# Sheet_1_2021-03-03.net
KiCad netlist of a schematic drawn in Altium Designer
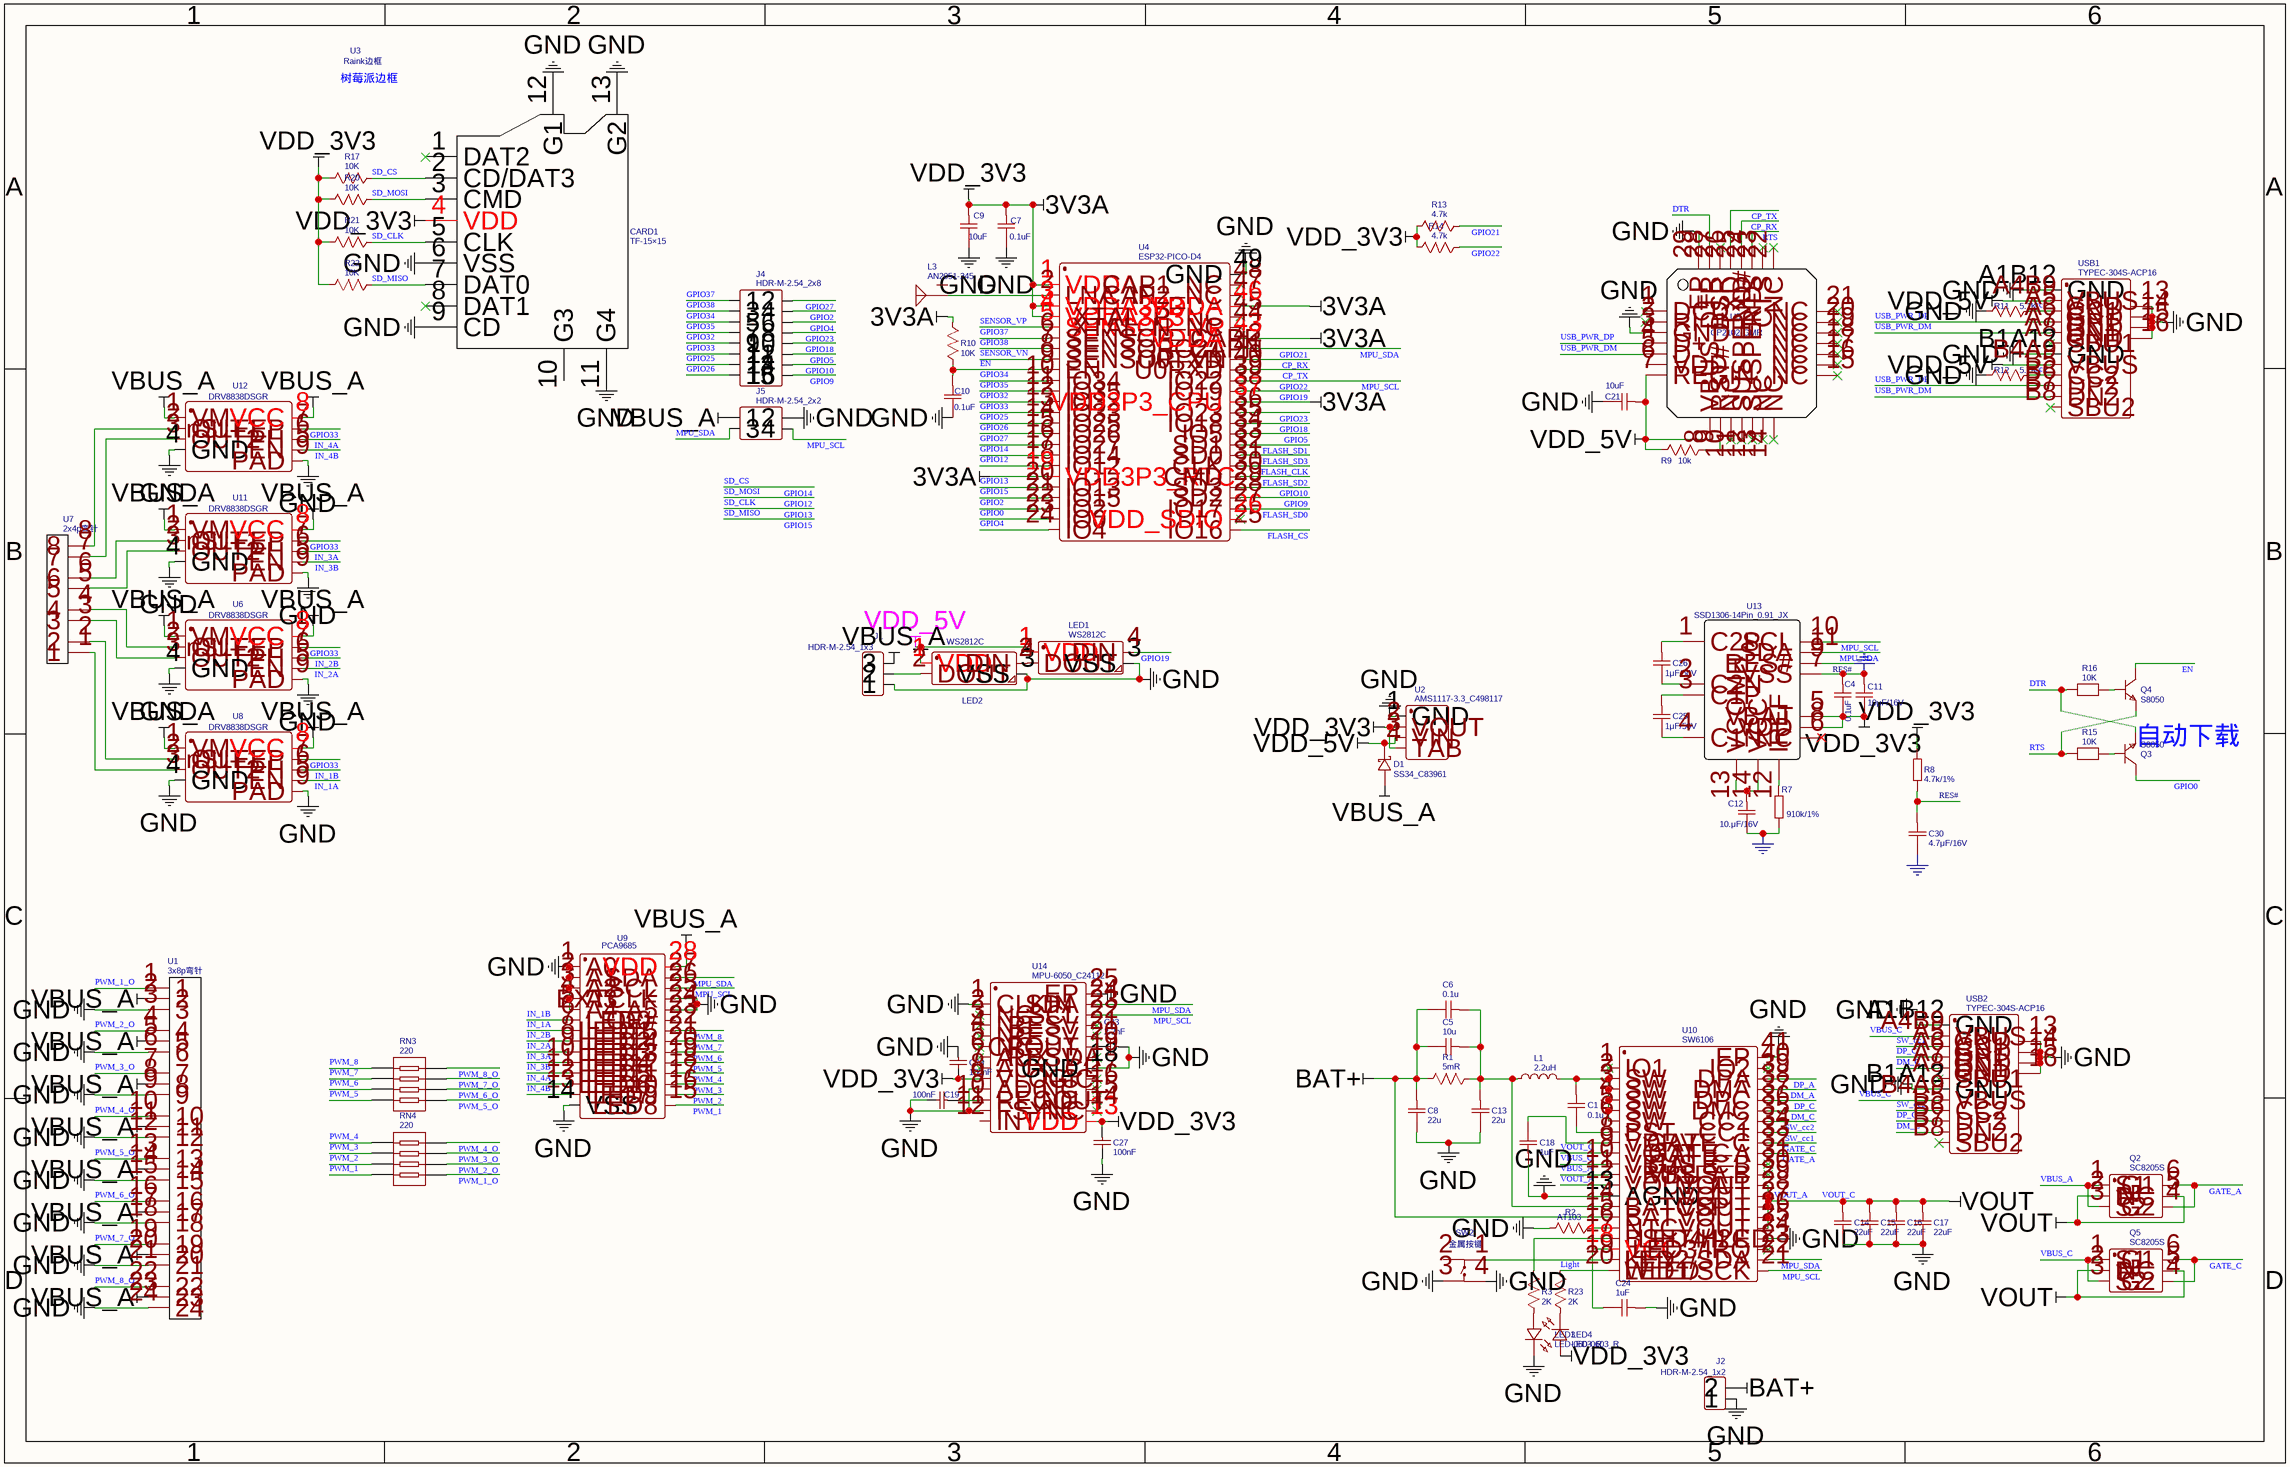
[diagram p0: Sheet_1_2021-03-03.schdoc]

(export (version "E")
  (design (tool "Eeschema 10.0.6"))
  (components
    (comp (ref "C1")
      (value "0.1u")
      (fields (field (name "CONTRIBUTOR") "LCEDA_Lib"))
      (libsource (lib "altium-import") (part "root_1_0.1u_"))
    )
    (comp (ref "C4")
      (value "0.1uF")
      (fields (field (name "CONTRIBUTOR") "LCEDA_Lib"))
      (libsource (lib "altium-import") (part "root_1_0.1uF_"))
    )
    (comp (ref "C5")
      (value "10u")
      (fields (field (name "CONTRIBUTOR") "LCEDA_Lib"))
      (libsource (lib "altium-import") (part "root_0_10u_"))
    )
    (comp (ref "C6")
      (value "0.1u")
      (fields (field (name "CONTRIBUTOR") "LCEDA_Lib"))
      (libsource (lib "altium-import") (part "root_0_0.1u_"))
    )
    (comp (ref "C7")
      (value "0.1uF")
      (fields (field (name "CONTRIBUTOR") "LCEDA_Lib"))
      (libsource (lib "altium-import") (part "root_1_0.1uF_"))
    )
    (comp (ref "C8")
      (value "22u")
      (fields (field (name "CONTRIBUTOR") "LCEDA_Lib"))
      (libsource (lib "altium-import") (part "root_1_22u_"))
    )
    (comp (ref "C9")
      (value "10uF")
      (fields (field (name "CONTRIBUTOR") "LCEDA_Lib"))
      (libsource (lib "altium-import") (part "root_1_10uF_"))
    )
    (comp (ref "C10")
      (value "0.1uF")
      (fields (field (name "CONTRIBUTOR") "LCEDA_Lib"))
      (libsource (lib "altium-import") (part "root_1_0.1uF_"))
    )
    (comp (ref "C11")
      (value "10μF/16V")
      (fields
        (field (name "BOM_SUPPLIER PART") "C326586")
        (field (name "BOM_MANUFACTURER PART") "CC0402KRX5R6BB475")
      )
      (libsource (lib "altium-import") (part "root_1_10μF/16V_"))
    )
    (comp (ref "C12")
      (value "10.μF/16V")
      (fields
        (field (name "BOM_SUPPLIER PART") "C326586")
        (field (name "BOM_MANUFACTURER PART") "CC0402KRX5R6BB475")
      )
      (libsource (lib "altium-import") (part "root_1_10.μF/16V_"))
    )
    (comp (ref "C13")
      (value "22u")
      (fields (field (name "CONTRIBUTOR") "LCEDA_Lib"))
      (libsource (lib "altium-import") (part "root_1_22u_"))
    )
    (comp (ref "C14")
      (value "22uF")
      (fields (field (name "CONTRIBUTOR") "LCEDA_Lib"))
      (libsource (lib "altium-import") (part "root_1_22uF_"))
    )
    (comp (ref "C15")
      (value "22uF")
      (fields (field (name "CONTRIBUTOR") "LCEDA_Lib"))
      (libsource (lib "altium-import") (part "root_1_22uF_"))
    )
    (comp (ref "C16")
      (value "22uF")
      (fields (field (name "CONTRIBUTOR") "LCEDA_Lib"))
      (libsource (lib "altium-import") (part "root_1_22uF_"))
    )
    (comp (ref "C17")
      (value "22uF")
      (fields (field (name "CONTRIBUTOR") "LCEDA_Lib"))
      (libsource (lib "altium-import") (part "root_1_22uF_"))
    )
    (comp (ref "C18")
      (value "1uF")
      (fields (field (name "CONTRIBUTOR") "LCEDA_Lib"))
      (libsource (lib "altium-import") (part "root_3_1uF_"))
    )
    (comp (ref "C19")
      (value "100nF")
      (fields
        (field (name "BOM_MANUFACTURER PART") "CL05B104KO5NNNC")
        (field (name "BOM_SUPPLIER PART") "C1525")
      )
      (libsource (lib "altium-import") (part "root_2_100nF_"))
    )
    (comp (ref "C21")
      (value "10uF")
      (fields (field (name "CONTRIBUTOR") "LCEDA_Lib"))
      (libsource (lib "altium-import") (part "root_0_10uF_"))
    )
    (comp (ref "C24")
      (value "1uF")
      (fields (field (name "CONTRIBUTOR") "LCEDA_Lib"))
      (libsource (lib "altium-import") (part "root_0_1uF_"))
    )
    (comp (ref "C25")
      (value "1μF/50V")
      (fields
        (field (name "BOM_SUPPLIER PART") "C29266")
        (field (name "BOM_MANUFACTURER PART") "CL05A105KO5NNNC")
      )
      (libsource (lib "altium-import") (part "root_1_1μF/50V_"))
    )
    (comp (ref "C26")
      (value "1μF/50V")
      (fields
        (field (name "BOM_SUPPLIER PART") "C29266")
        (field (name "BOM_MANUFACTURER PART") "CL05A105KO5NNNC")
      )
      (libsource (lib "altium-import") (part "root_1_1μF/50V_"))
    )
    (comp (ref "C27")
      (value "100nF")
      (fields
        (field (name "BOM_MANUFACTURER PART") "CL05B104KO5NNNC")
        (field (name "BOM_SUPPLIER PART") "C1525")
      )
      (libsource (lib "altium-import") (part "root_3_100nF_"))
    )
    (comp (ref "C28")
      (value "100nF")
      (fields
        (field (name "BOM_MANUFACTURER PART") "CL05B104KO5NNNC")
        (field (name "BOM_SUPPLIER PART") "C1525")
      )
      (libsource (lib "altium-import") (part "root_3_100nF_"))
    )
    (comp (ref "C30")
      (value "4.7μF/16V")
      (fields
        (field (name "BOM_SUPPLIER PART") "C326586")
        (field (name "BOM_MANUFACTURER PART") "CC0402KRX5R6BB475")
      )
      (libsource (lib "altium-import") (part "root_1_4.7μF/16V_"))
    )
    (comp (ref "C33")
      (value "2.2nF")
      (fields
        (field (name "BOM_MANUFACTURER PART") "0603B222K500NT")
        (field (name "BOM_SUPPLIER PART") "C1604")
      )
      (libsource (lib "altium-import") (part "root_2_2.2nF_"))
    )
    (comp (ref "CARD1")
      (value "TF-15×15")
      (fields (field (name "BOM_SUPPLIER PART") "C111196"))
      (libsource (lib "altium-import") (part "root_0_TF-15×15_"))
    )
    (comp (ref "D1")
      (value "SS34_C83961")
      (fields (field (name "BOM_MANUFACTURER PART") "SS34") (field (name "BOM_SUPPLIER PART") "C83961"))
      (libsource (lib "altium-import") (part "root_3_SS34_C83961_"))
    )
    (comp (ref "J1")
      (value "HDR-M-2.54_1x3")
      (fields (field (name "BOM_SUPPLIER PART") "C180248") (field (name "CONTRIBUTOR") "LCEDA_Lib"))
      (libsource (lib "altium-import") (part "root_2_HDR-M-2.54_1x3_"))
    )
    (comp (ref "J2")
      (value "HDR-M-2.54_1x2")
      (fields (field (name "BOM_SUPPLIER PART") "C124375") (field (name "CONTRIBUTOR") "LCEDA_Lib"))
      (libsource (lib "altium-import") (part "root_2_HDR-M-2.54_1x2_"))
    )
    (comp (ref "J4")
      (value "HDR-M-2.54_2x8")
      (fields (field (name "BOM_SUPPLIER PART") "C68234") (field (name "CONTRIBUTOR") "LCEDA_Lib"))
      (libsource (lib "altium-import") (part "root_0_HDR-M-2.54_2x8_"))
    )
    (comp (ref "J5")
      (value "HDR-M-2.54_2x2")
      (fields (field (name "BOM_SUPPLIER PART") "C66690") (field (name "CONTRIBUTOR") "LCEDA_Lib"))
      (libsource (lib "altium-import") (part "root_0_HDR-M-2.54_2x2_"))
    )
    (comp (ref "L1")
      (value "2.2uH")
      (fields
        (field (name "BOM_SUPPLIER PART") "C497893")
        (field (name "BOM_MANUFACTURER PART") "YSPI1050-2R2M")
        (field (name "CONTRIBUTOR") "LCSC")
      )
      (libsource (lib "altium-import") (part "root_0_2.2uH_"))
    )
    (comp (ref "L3")
      (value "AN2051-245")
      (fields (field (name "BOM_SUPPLIER PART") "C99727"))
      (libsource (lib "altium-import") (part "root_1_AN2051-245_"))
    )
    (comp (ref "LED1")
      (value "WS2812C")
      (fields (field (name "BOM_SUPPLIER PART") "C114587") (field (name "CONTRIBUTOR") "LCSC"))
      (libsource (lib "altium-import") (part "root_0_WS2812C_"))
    )
    (comp (ref "LED2")
      (value "WS2812C")
      (fields (field (name "BOM_SUPPLIER PART") "C114587") (field (name "CONTRIBUTOR") "LCSC"))
      (libsource (lib "altium-import") (part "root_0_WS2812C_"))
    )
    (comp (ref "LED3")
      (value "LED-0603_R")
      (fields
        (field (name "BOM_MANUFACTURER PART") "19-217/R6C-AL1M2VY/3T")
        (field (name "BOM_SUPPLIER PART") "C72044")
        (field (name "CONTRIBUTOR") "LCEDA_01")
      )
      (libsource (lib "altium-import") (part "root_3_LED-0603_R_"))
    )
    (comp (ref "LED4")
      (value "LED-0603_R")
      (fields
        (field (name "BOM_MANUFACTURER PART") "19-217/R6C-AL1M2VY/3T")
        (field (name "BOM_SUPPLIER PART") "C72044")
        (field (name "CONTRIBUTOR") "LCEDA_01")
      )
      (libsource (lib "altium-import") (part "root_1_LED-0603_R_"))
    )
    (comp (ref "Q2")
      (value "SC8205S")
      (fields (field (name "BOM_SUPPLIER PART") "C84684"))
      (libsource (lib "altium-import") (part "root_0_SC8205S_"))
    )
    (comp (ref "Q3")
      (value "S8050")
      (fields (field (name "BOM_SUPPLIER PART") "C414195") (field (name "CONTRIBUTOR") "LCSC"))
      (libsource (lib "altium-import") (part "root_0_S8050_"))
    )
    (comp (ref "Q4")
      (value "S8050")
      (fields (field (name "BOM_SUPPLIER PART") "C414195") (field (name "CONTRIBUTOR") "LCSC"))
      (libsource (lib "") (part "root_0_S8050__1"))
    )
    (comp (ref "Q5")
      (value "SC8205S")
      (fields (field (name "BOM_SUPPLIER PART") "C84684"))
      (libsource (lib "altium-import") (part "root_0_SC8205S_"))
    )
    (comp (ref "R1")
      (value "5mR")
      (fields (field (name "CONTRIBUTOR") "LCEDA_Lib"))
      (libsource (lib "altium-import") (part "root_0_5mR_"))
    )
    (comp (ref "R2")
      (value "AT103")
      (fields (field (name "CONTRIBUTOR") "LCEDA_Lib"))
      (libsource (lib "altium-import") (part "root_0_AT103_"))
    )
    (comp (ref "R3")
      (value "2K")
      (fields (field (name "CONTRIBUTOR") "LCEDA_Lib"))
      (libsource (lib "altium-import") (part "root_1_2K_"))
    )
    (comp (ref "R7")
      (value "910k/1%")
      (fields
        (field (name "BOM_SUPPLIER PART") "C137927")
        (field (name "BOM_MANUFACTURER PART") "RC0402FR-07910KL")
      )
      (libsource (lib "altium-import") (part "root_1_910k/1%_"))
    )
    (comp (ref "R8")
      (value "4.7k/1%")
      (fields
        (field (name "BOM_SUPPLIER PART") "C326586")
        (field (name "BOM_MANUFACTURER PART") "CC0402KRX5R6BB475")
      )
      (libsource (lib "altium-import") (part "root_1_4.7k/1%_"))
    )
    (comp (ref "R9")
      (value "10k")
      (fields (field (name "CONTRIBUTOR") "LCEDA_Lib"))
      (libsource (lib "altium-import") (part "root_0_10k_"))
    )
    (comp (ref "R10")
      (value "10K")
      (fields (field (name "CONTRIBUTOR") "LCEDA_Lib"))
      (libsource (lib "altium-import") (part "root_1_10K_"))
    )
    (comp (ref "R11")
      (value "5.1K")
      (fields (field (name "CONTRIBUTOR") "LCEDA_Lib"))
      (libsource (lib "altium-import") (part "root_2_5.1K_"))
    )
    (comp (ref "R12")
      (value "5.1K")
      (fields (field (name "CONTRIBUTOR") "LCEDA_Lib"))
      (libsource (lib "altium-import") (part "root_2_5.1K_"))
    )
    (comp (ref "R13")
      (value "4.7k")
      (fields (field (name "CONTRIBUTOR") "LCEDA_Lib"))
      (libsource (lib "altium-import") (part "root_0_4.7k_"))
    )
    (comp (ref "R14")
      (value "4.7k")
      (fields (field (name "CONTRIBUTOR") "LCEDA_Lib"))
      (libsource (lib "altium-import") (part "root_0_4.7k_"))
    )
    (comp (ref "R15")
      (value "10K")
      (fields
        (field (name "BOM_SUPPLIER PART") "C723584")
        (field (name "BOM_MANUFACTURER PART") "RT0402FRD0710KL")
        (field (name "CONTRIBUTOR") "LCSC")
      )
      (libsource (lib "") (part "root_0_10K__1"))
    )
    (comp (ref "R16")
      (value "10K")
      (fields
        (field (name "BOM_SUPPLIER PART") "C723584")
        (field (name "BOM_MANUFACTURER PART") "RT0402FRD0710KL")
        (field (name "CONTRIBUTOR") "LCSC")
      )
      (libsource (lib "") (part "root_0_10K__1"))
    )
    (comp (ref "R17")
      (value "10K")
      (fields (field (name "CONTRIBUTOR") "LCEDA_Lib"))
      (libsource (lib "altium-import") (part "root_0_10K_"))
    )
    (comp (ref "R20")
      (value "10K")
      (fields (field (name "CONTRIBUTOR") "LCEDA_Lib"))
      (libsource (lib "altium-import") (part "root_0_10K_"))
    )
    (comp (ref "R21")
      (value "10K")
      (fields (field (name "CONTRIBUTOR") "LCEDA_Lib"))
      (libsource (lib "altium-import") (part "root_0_10K_"))
    )
    (comp (ref "R22")
      (value "10K")
      (fields (field (name "CONTRIBUTOR") "LCEDA_Lib"))
      (libsource (lib "altium-import") (part "root_0_10K_"))
    )
    (comp (ref "R23")
      (value "2K")
      (fields (field (name "CONTRIBUTOR") "LCEDA_Lib"))
      (libsource (lib "altium-import") (part "root_1_2K_"))
    )
    (comp (ref "RN3")
      (value "220")
      (fields
        (field (name "BOM_MANUFACTURER PART") "4D03WGJ0330T5E")
        (field (name "BOM_SUPPLIER PART") "C25508")
      )
      (libsource (lib "altium-import") (part "root_0_220_"))
    )
    (comp (ref "RN4")
      (value "220")
      (fields
        (field (name "BOM_MANUFACTURER PART") "4D03WGJ0330T5E")
        (field (name "BOM_SUPPLIER PART") "C25508")
      )
      (libsource (lib "altium-import") (part "root_0_220_"))
    )
    (comp (ref "SW2")
      (value "金属按键")
      (fields
        (field (name "BOM_SUPPLIER PART") "C692460")
        (field (name "BOM_MANUFACTURER PART") "TS-1187A-B-C-B")
        (field (name "CONTRIBUTOR") "LCSC")
      )
      (libsource (lib "altium-import") (part "root_0_金属按键_"))
    )
    (comp (ref "U1")
      (value "3x8p弯针")
      (fields (field (name "CONTRIBUTOR") "Jyishit"))
      (libsource (lib "altium-import") (part "root_0_3x8p弯针_"))
    )
    (comp (ref "U2")
      (value "AMS1117-3.3_C498117")
      (fields
        (field (name "BOM_SUPPLIER PART") "C498117")
        (field (name "BOM_MANUFACTURER PART") "AMS1117-3.3")
        (field (name "CONTRIBUTOR") "LCSC")
      )
      (libsource (lib "altium-import") (part "root_0_AMS1117-3.3_C498117_"))
    )
    (comp (ref "U3")
      (value "Raink边框")
      (fields (field (name "CONTRIBUTOR") "Jyishit"))
      (libsource (lib "altium-import") (part "root_0_Raink边框_"))
    )
    (comp (ref "U4")
      (value "ESP32-PICO-D4")
      (fields (field (name "BOM_SUPPLIER PART") "C193707") (field (name "CONTRIBUTOR") "LCSC"))
      (libsource (lib "altium-import") (part "root_0_ESP32-PICO-D4_"))
    )
    (comp (ref "U5")
      (value "CP2102-GMR")
      (fields (field (name "BOM_SUPPLIER PART") "C6568"))
      (libsource (lib "altium-import") (part "root_0_CP2102-GMR_"))
    )
    (comp (ref "U6")
      (value "DRV8838DSGR")
      (fields (field (name "BOM_SUPPLIER PART") "C86667"))
      (libsource (lib "altium-import") (part "root_0_DRV8838DSGR_"))
    )
    (comp (ref "U7")
      (value "2x4p弯针")
      (fields (field (name "CONTRIBUTOR") "SinKy"))
      (libsource (lib "altium-import") (part "root_2_2x4p弯针_"))
    )
    (comp (ref "U8")
      (value "DRV8838DSGR")
      (fields (field (name "BOM_SUPPLIER PART") "C86667"))
      (libsource (lib "altium-import") (part "root_0_DRV8838DSGR_"))
    )
    (comp (ref "U9")
      (value "PCA9685")
      (fields
        (field (name "BOM_MANUFACTURER PART") "PCA9685PW/Q900,118")
        (field (name "BOM_SUPPLIER PART") "C92206")
      )
      (libsource (lib "altium-import") (part "root_0_PCA9685_"))
    )
    (comp (ref "U10")
      (value "SW6106")
      (fields (field (name "BOM_SUPPLIER PART") "C406803") (field (name "CONTRIBUTOR") "LCSC"))
      (libsource (lib "altium-import") (part "root_0_SW6106_"))
    )
    (comp (ref "U11")
      (value "DRV8838DSGR")
      (fields (field (name "BOM_SUPPLIER PART") "C86667"))
      (libsource (lib "altium-import") (part "root_0_DRV8838DSGR_"))
    )
    (comp (ref "U12")
      (value "DRV8838DSGR")
      (fields (field (name "BOM_SUPPLIER PART") "C86667"))
      (libsource (lib "altium-import") (part "root_0_DRV8838DSGR_"))
    )
    (comp (ref "U13")
      (value "SSD1306-14Pin_0.91_JX")
      (libsource (lib "altium-import") (part "root_0_SSD1306-14Pin_0.91_JX_"))
    )
    (comp (ref "U14")
      (value "MPU-6050_C24112")
      (fields (field (name "BOM_MANUFACTURER PART") "MPU-6050") (field (name "BOM_SUPPLIER PART") "C24112"))
      (libsource (lib "altium-import") (part "root_0_MPU-6050_C24112_"))
    )
    (comp (ref "USB1")
      (value "TYPEC-304S-ACP16")
      (fields (field (name "BOM_SUPPLIER PART") "C720630") (field (name "CONTRIBUTOR") "LCSC"))
      (libsource (lib "altium-import") (part "root_0_TYPEC-304S-ACP16_"))
    )
    (comp (ref "USB2")
      (value "TYPEC-304S-ACP16")
      (fields (field (name "BOM_SUPPLIER PART") "C720630") (field (name "CONTRIBUTOR") "LCSC"))
      (libsource (lib "altium-import") (part "root_0_TYPEC-304S-ACP16_"))
    )
  )
  (nets
    (net (code "1") (name "/CP_RX") (class "Default")
      (node (ref "U4") (pin "41") (pinfunction "U0TXD_41") (pintype "passive"))
      (node (ref "U5") (pin "25") (pinfunction "RXD_25") (pintype "passive"))
    )
    (net (code "2") (name "/CP_TX") (class "Default")
      (node (ref "U4") (pin "40") (pinfunction "U0RXD_40") (pintype "passive"))
      (node (ref "U5") (pin "26") (pinfunction "TXD_26") (pintype "passive"))
    )
    (net (code "3") (name "/DM_A") (class "Default")
      (node (ref "U10") (pin "38") (pinfunction "DMA_38") (pintype "passive"))
    )
    (net (code "4") (name "/DM_C") (class "Default")
      (node (ref "U10") (pin "36") (pinfunction "DMC_36") (pintype "passive"))
      (node (ref "USB2") (pin "A7") (pinfunction "DN1_A7") (pintype "passive"))
      (node (ref "USB2") (pin "B7") (pinfunction "DN2_B7") (pintype "passive"))
    )
    (net (code "5") (name "/DP_A") (class "Default")
      (node (ref "U10") (pin "39") (pinfunction "DPA_39") (pintype "passive"))
    )
    (net (code "6") (name "/DP_C") (class "Default")
      (node (ref "U10") (pin "37") (pinfunction "DPC_37") (pintype "passive"))
      (node (ref "USB2") (pin "A6") (pinfunction "DP1_A6") (pintype "passive"))
      (node (ref "USB2") (pin "B6") (pinfunction "DP2_B6") (pintype "passive"))
    )
    (net (code "7") (name "/DTR") (class "Default")
      (node (ref "Q3") (pin "2") (pinfunction "E_2") (pintype "passive"))
      (node (ref "R16") (pin "1") (pinfunction "1_1") (pintype "passive"))
      (node (ref "U5") (pin "28") (pinfunction "DTR_28") (pintype "passive"))
    )
    (net (code "8") (name "/EN") (class "Default")
      (node (ref "C10") (pin "2") (pinfunction "2_2") (pintype "passive"))
      (node (ref "Q4") (pin "3") (pinfunction "C_3") (pintype "passive"))
      (node (ref "R10") (pin "1") (pinfunction "1_1") (pintype "passive"))
      (node (ref "U4") (pin "9") (pinfunction "EN_9") (pintype "passive"))
    )
    (net (code "9") (name "/FLASH_CLK") (class "Default")
      (node (ref "U4") (pin "31") (pinfunction "CLK_31") (pintype "passive"))
    )
    (net (code "10") (name "/FLASH_CS") (class "Default")
      (node (ref "U4") (pin "25") (pinfunction "IO16_25") (pintype "passive"))
    )
    (net (code "11") (name "/FLASH_SD0") (class "Default")
      (node (ref "U4") (pin "27") (pinfunction "IO17_27") (pintype "passive"))
    )
    (net (code "12") (name "/FLASH_SD1") (class "Default")
      (node (ref "U4") (pin "33") (pinfunction "SD1_33") (pintype "passive"))
    )
    (net (code "13") (name "/FLASH_SD2") (class "Default")
      (node (ref "U4") (pin "30") (pinfunction "CMD_30") (pintype "passive"))
    )
    (net (code "14") (name "/FLASH_SD3") (class "Default")
      (node (ref "U4") (pin "32") (pinfunction "SD0_32") (pintype "passive"))
    )
    (net (code "15") (name "/GATE_A") (class "Default")
      (node (ref "Q2") (pin "4") (pinfunction "G2_4") (pintype "passive"))
      (node (ref "Q2") (pin "6") (pinfunction "G1_6") (pintype "passive"))
      (node (ref "U10") (pin "32") (pinfunction "GATE_A_32") (pintype "passive"))
    )
    (net (code "16") (name "/GATE_C") (class "Default")
      (node (ref "Q5") (pin "4") (pinfunction "G2_4") (pintype "passive"))
      (node (ref "Q5") (pin "6") (pinfunction "G1_6") (pintype "passive"))
      (node (ref "U10") (pin "33") (pinfunction "GATE_C_33") (pintype "passive"))
    )
    (net (code "17") (name "/GPIO0") (class "Default")
      (node (ref "Q3") (pin "3") (pinfunction "C_3") (pintype "passive"))
      (node (ref "U4") (pin "23") (pinfunction "IO0_23") (pintype "passive"))
    )
    (net (code "18") (name "/GPIO2") (class "Default")
      (node (ref "J4") (pin "4") (pinfunction "4_4") (pintype "passive"))
      (node (ref "U4") (pin "22") (pinfunction "IO2_22") (pintype "passive"))
    )
    (net (code "19") (name "/GPIO4") (class "Default")
      (node (ref "J4") (pin "6") (pinfunction "6_6") (pintype "passive"))
      (node (ref "U4") (pin "24") (pinfunction "IO4_24") (pintype "passive"))
    )
    (net (code "20") (name "/GPIO5") (class "Default")
      (node (ref "J4") (pin "12") (pinfunction "12_12") (pintype "passive"))
      (node (ref "U4") (pin "34") (pinfunction "IO5_34") (pintype "passive"))
    )
    (net (code "21") (name "/GPIO9") (class "Default")
      (node (ref "J4") (pin "16") (pinfunction "16_16") (pintype "passive"))
      (node (ref "U4") (pin "28") (pinfunction "SD2_28") (pintype "passive"))
    )
    (net (code "22") (name "/GPIO10") (class "Default")
      (node (ref "J4") (pin "14") (pinfunction "14_14") (pintype "passive"))
      (node (ref "U4") (pin "29") (pinfunction "SD3_29") (pintype "passive"))
    )
    (net (code "23") (name "/GPIO12") (class "Default")
      (node (ref "CARD1") (pin "3") (pinfunction "CMD_3") (pintype "passive"))
      (node (ref "R20") (pin "2") (pinfunction "2_2") (pintype "passive"))
      (node (ref "U4") (pin "18") (pinfunction "IO12_18") (pintype "passive"))
    )
    (net (code "24") (name "/GPIO13") (class "Default")
      (node (ref "CARD1") (pin "5") (pinfunction "CLK_5") (pintype "passive"))
      (node (ref "R21") (pin "2") (pinfunction "2_2") (pintype "passive"))
      (node (ref "U4") (pin "20") (pinfunction "IO13_20") (pintype "passive"))
    )
    (net (code "25") (name "/GPIO14") (class "Default")
      (node (ref "CARD1") (pin "2") (pinfunction "CD/DAT3_2") (pintype "passive"))
      (node (ref "R17") (pin "2") (pinfunction "2_2") (pintype "passive"))
      (node (ref "U4") (pin "17") (pinfunction "IO14_17") (pintype "passive"))
    )
    (net (code "26") (name "/GPIO15") (class "Default")
      (node (ref "CARD1") (pin "7") (pinfunction "DAT0_7") (pintype "passive"))
      (node (ref "R22") (pin "2") (pinfunction "2_2") (pintype "passive"))
      (node (ref "U4") (pin "21") (pinfunction "IO15_21") (pintype "passive"))
    )
    (net (code "27") (name "/GPIO18") (class "Default")
      (node (ref "J4") (pin "10") (pinfunction "10_10") (pintype "passive"))
      (node (ref "U4") (pin "35") (pinfunction "IO18_35") (pintype "passive"))
    )
    (net (code "28") (name "/GPIO19") (class "Default")
      (node (ref "LED1") (pin "4") (pinfunction "DIN_4") (pintype "passive"))
      (node (ref "U4") (pin "38") (pinfunction "IO19_38") (pintype "passive"))
    )
    (net (code "29") (name "/GPIO21") (class "Default")
      (node (ref "J5") (pin "3") (pinfunction "3_3") (pintype "passive"))
      (node (ref "R13") (pin "2") (pinfunction "2_2") (pintype "passive"))
      (node (ref "U10") (pin "22") (pinfunction "LED2/SDA_22") (pintype "passive"))
      (node (ref "U13") (pin "11") (pinfunction "SDA_11") (pintype "passive"))
      (node (ref "U14") (pin "24") (pinfunction "SDA_24") (pintype "passive"))
      (node (ref "U4") (pin "42") (pinfunction "IO21_42") (pintype "passive"))
      (node (ref "U9") (pin "27") (pinfunction "SDA_27") (pintype "passive"))
    )
    (net (code "30") (name "/GPIO22") (class "Default")
      (node (ref "J5") (pin "4") (pinfunction "4_4") (pintype "passive"))
      (node (ref "R14") (pin "2") (pinfunction "2_2") (pintype "passive"))
      (node (ref "U10") (pin "21") (pinfunction "LED1/SCK_21") (pintype "passive"))
      (node (ref "U13") (pin "10") (pinfunction "SCL_10") (pintype "passive"))
      (node (ref "U14") (pin "23") (pinfunction "SCL_23") (pintype "passive"))
      (node (ref "U4") (pin "39") (pinfunction "IO22_39") (pintype "passive"))
      (node (ref "U9") (pin "26") (pinfunction "SCL_26") (pintype "passive"))
    )
    (net (code "31") (name "/GPIO23") (class "Default")
      (node (ref "J4") (pin "8") (pinfunction "8_8") (pintype "passive"))
      (node (ref "U4") (pin "36") (pinfunction "IO23_36") (pintype "passive"))
    )
    (net (code "32") (name "/GPIO25") (class "Default")
      (node (ref "J4") (pin "13") (pinfunction "13_13") (pintype "passive"))
      (node (ref "U4") (pin "14") (pinfunction "IO25_14") (pintype "passive"))
    )
    (net (code "33") (name "/GPIO26") (class "Default")
      (node (ref "J4") (pin "15") (pinfunction "15_15") (pintype "passive"))
      (node (ref "U4") (pin "15") (pinfunction "IO26_15") (pintype "passive"))
    )
    (net (code "34") (name "/GPIO27") (class "Default")
      (node (ref "J4") (pin "2") (pinfunction "2_2") (pintype "passive"))
      (node (ref "U4") (pin "16") (pinfunction "IO27_16") (pintype "passive"))
    )
    (net (code "35") (name "/GPIO32") (class "Default")
      (node (ref "J4") (pin "9") (pinfunction "9_9") (pintype "passive"))
      (node (ref "U4") (pin "12") (pinfunction "IO32_12") (pintype "passive"))
    )
    (net (code "36") (name "/GPIO33") (class "Default")
      (node (ref "J4") (pin "11") (pinfunction "11_11") (pintype "passive"))
      (node (ref "U11") (pin "7") (pinfunction "nSLEEP_7") (pintype "passive"))
      (node (ref "U12") (pin "7") (pinfunction "nSLEEP_7") (pintype "passive"))
      (node (ref "U4") (pin "13") (pinfunction "IO33_13") (pintype "passive"))
      (node (ref "U6") (pin "7") (pinfunction "nSLEEP_7") (pintype "passive"))
      (node (ref "U8") (pin "7") (pinfunction "nSLEEP_7") (pintype "passive"))
    )
    (net (code "37") (name "/GPIO34") (class "Default")
      (node (ref "J4") (pin "5") (pinfunction "5_5") (pintype "passive"))
      (node (ref "U4") (pin "10") (pinfunction "IO34_10") (pintype "passive"))
    )
    (net (code "38") (name "/GPIO35") (class "Default")
      (node (ref "J4") (pin "7") (pinfunction "7_7") (pintype "passive"))
      (node (ref "U4") (pin "11") (pinfunction "IO35_11") (pintype "passive"))
    )
    (net (code "39") (name "/GPIO37") (class "Default")
      (node (ref "J4") (pin "1") (pinfunction "1_1") (pintype "passive"))
      (node (ref "U4") (pin "6") (pinfunction "SENSOR_CAPP_6") (pintype "passive"))
    )
    (net (code "40") (name "/GPIO38") (class "Default")
      (node (ref "J4") (pin "3") (pinfunction "3_3") (pintype "passive"))
      (node (ref "U4") (pin "7") (pinfunction "SENSOR_CAPN_7") (pintype "passive"))
    )
    (net (code "41") (name "/IN_1A") (class "Default")
      (node (ref "U8") (pin "5") (pinfunction "EN_5") (pintype "passive"))
      (node (ref "U9") (pin "7") (pinfunction "LED1_7") (pintype "passive"))
    )
    (net (code "42") (name "/IN_1B") (class "Default")
      (node (ref "U8") (pin "6") (pinfunction "PH_6") (pintype "passive"))
      (node (ref "U9") (pin "6") (pinfunction "LED0_6") (pintype "passive"))
    )
    (net (code "43") (name "/IN_2A") (class "Default")
      (node (ref "U6") (pin "5") (pinfunction "EN_5") (pintype "passive"))
      (node (ref "U9") (pin "9") (pinfunction "LED3_9") (pintype "passive"))
    )
    (net (code "44") (name "/IN_2B") (class "Default")
      (node (ref "U6") (pin "6") (pinfunction "PH_6") (pintype "passive"))
      (node (ref "U9") (pin "8") (pinfunction "LED2_8") (pintype "passive"))
    )
    (net (code "45") (name "/IN_3A") (class "Default")
      (node (ref "U11") (pin "6") (pinfunction "PH_6") (pintype "passive"))
      (node (ref "U9") (pin "10") (pinfunction "LED4_10") (pintype "passive"))
    )
    (net (code "46") (name "/IN_3B") (class "Default")
      (node (ref "U11") (pin "5") (pinfunction "EN_5") (pintype "passive"))
      (node (ref "U9") (pin "11") (pinfunction "LED5_11") (pintype "passive"))
    )
    (net (code "47") (name "/IN_4A") (class "Default")
      (node (ref "U12") (pin "6") (pinfunction "PH_6") (pintype "passive"))
      (node (ref "U9") (pin "12") (pinfunction "LED6_12") (pintype "passive"))
    )
    (net (code "48") (name "/IN_4B") (class "Default")
      (node (ref "U12") (pin "5") (pinfunction "EN_5") (pintype "passive"))
      (node (ref "U9") (pin "13") (pinfunction "LED7_13") (pintype "passive"))
    )
    (net (code "49") (name "/Light") (class "Default")
      (node (ref "R23") (pin "2") (pinfunction "2_2") (pintype "passive"))
      (node (ref "U10") (pin "20") (pinfunction "WLED_20") (pintype "passive"))
    )
    (net (code "50") (name "/PWM_1") (class "Default")
      (node (ref "RN4") (pin "4") (pinfunction "4_4") (pintype "passive"))
      (node (ref "U9") (pin "15") (pinfunction "LED8_15") (pintype "passive"))
    )
    (net (code "51") (name "/PWM_1_O") (class "Default")
      (node (ref "RN4") (pin "5") (pinfunction "5_5") (pintype "passive"))
      (node (ref "U1") (pin "1") (pinfunction "1_1") (pintype "passive"))
    )
    (net (code "52") (name "/PWM_2") (class "Default")
      (node (ref "RN4") (pin "3") (pinfunction "3_3") (pintype "passive"))
      (node (ref "U9") (pin "16") (pinfunction "LED9_16") (pintype "passive"))
    )
    (net (code "53") (name "/PWM_2_O") (class "Default")
      (node (ref "RN4") (pin "6") (pinfunction "6_6") (pintype "passive"))
      (node (ref "U1") (pin "4") (pinfunction "4_4") (pintype "passive"))
    )
    (net (code "54") (name "/PWM_3") (class "Default")
      (node (ref "RN4") (pin "2") (pinfunction "2_2") (pintype "passive"))
      (node (ref "U9") (pin "17") (pinfunction "LED10_17") (pintype "passive"))
    )
    (net (code "55") (name "/PWM_3_O") (class "Default")
      (node (ref "RN4") (pin "7") (pinfunction "7_7") (pintype "passive"))
      (node (ref "U1") (pin "7") (pinfunction "7_7") (pintype "passive"))
    )
    (net (code "56") (name "/PWM_4") (class "Default")
      (node (ref "RN4") (pin "1") (pinfunction "1_1") (pintype "passive"))
      (node (ref "U9") (pin "18") (pinfunction "LED11_18") (pintype "passive"))
    )
    (net (code "57") (name "/PWM_4_O") (class "Default")
      (node (ref "RN4") (pin "8") (pinfunction "8_8") (pintype "passive"))
      (node (ref "U1") (pin "10") (pinfunction "10_10") (pintype "passive"))
    )
    (net (code "58") (name "/PWM_5") (class "Default")
      (node (ref "RN3") (pin "4") (pinfunction "4_4") (pintype "passive"))
      (node (ref "U9") (pin "19") (pinfunction "LED12_19") (pintype "passive"))
    )
    (net (code "59") (name "/PWM_5_O") (class "Default")
      (node (ref "RN3") (pin "5") (pinfunction "5_5") (pintype "passive"))
      (node (ref "U1") (pin "13") (pinfunction "13_13") (pintype "passive"))
    )
    (net (code "60") (name "/PWM_6") (class "Default")
      (node (ref "RN3") (pin "3") (pinfunction "3_3") (pintype "passive"))
      (node (ref "U9") (pin "20") (pinfunction "LED13_20") (pintype "passive"))
    )
    (net (code "61") (name "/PWM_6_O") (class "Default")
      (node (ref "RN3") (pin "6") (pinfunction "6_6") (pintype "passive"))
      (node (ref "U1") (pin "16") (pinfunction "16_16") (pintype "passive"))
    )
    (net (code "62") (name "/PWM_7") (class "Default")
      (node (ref "RN3") (pin "2") (pinfunction "2_2") (pintype "passive"))
      (node (ref "U9") (pin "21") (pinfunction "LED14_21") (pintype "passive"))
    )
    (net (code "63") (name "/PWM_7_O") (class "Default")
      (node (ref "RN3") (pin "7") (pinfunction "7_7") (pintype "passive"))
      (node (ref "U1") (pin "19") (pinfunction "19_19") (pintype "passive"))
    )
    (net (code "64") (name "/PWM_8") (class "Default")
      (node (ref "RN3") (pin "1") (pinfunction "1_1") (pintype "passive"))
      (node (ref "U9") (pin "22") (pinfunction "LED15_22") (pintype "passive"))
    )
    (net (code "65") (name "/PWM_8_O") (class "Default")
      (node (ref "RN3") (pin "8") (pinfunction "8_8") (pintype "passive"))
      (node (ref "U1") (pin "22") (pinfunction "22_22") (pintype "passive"))
    )
    (net (code "66") (name "/RES#") (class "Default")
      (node (ref "C30") (pin "2") (pinfunction "2_2") (pintype "passive"))
      (node (ref "R8") (pin "1") (pinfunction "1_1") (pintype "passive"))
      (node (ref "U13") (pin "9") (pinfunction "RES#_9") (pintype "passive"))
    )
    (net (code "67") (name "/RTS") (class "Default")
      (node (ref "Q4") (pin "2") (pinfunction "E_2") (pintype "passive"))
      (node (ref "R15") (pin "1") (pinfunction "1_1") (pintype "passive"))
      (node (ref "U5") (pin "24") (pinfunction "RTS_24") (pintype "passive"))
    )
    (net (code "68") (name "/SENSOR_VN") (class "Default")
      (node (ref "U4") (pin "8") (pinfunction "SENSOR_VN_8") (pintype "passive"))
    )
    (net (code "69") (name "/SENSOR_VP") (class "Default")
      (node (ref "U4") (pin "5") (pinfunction "SENSOR_VP_5") (pintype "passive"))
    )
    (net (code "70") (name "/SW_cc1") (class "Default")
      (node (ref "U10") (pin "34") (pinfunction "CC1_34") (pintype "passive"))
      (node (ref "USB2") (pin "A5") (pinfunction "CC1_A5") (pintype "passive"))
    )
    (net (code "71") (name "/SW_cc2") (class "Default")
      (node (ref "U10") (pin "35") (pinfunction "CC2_35") (pintype "passive"))
      (node (ref "USB2") (pin "B5") (pinfunction "CC2_B5") (pintype "passive"))
    )
    (net (code "72") (name "/USB_PWR_DM") (class "Default")
      (node (ref "U5") (pin "5") (pinfunction "D-_5") (pintype "passive"))
      (node (ref "USB1") (pin "A7") (pinfunction "DN1_A7") (pintype "passive"))
      (node (ref "USB1") (pin "B7") (pinfunction "DN2_B7") (pintype "passive"))
    )
    (net (code "73") (name "/USB_PWR_DP") (class "Default")
      (node (ref "U5") (pin "4") (pinfunction "D+_4") (pintype "passive"))
      (node (ref "USB1") (pin "A6") (pinfunction "DP1_A6") (pintype "passive"))
      (node (ref "USB1") (pin "B6") (pinfunction "DP2_B6") (pintype "passive"))
    )
    (net (code "74") (name "/VBUS_C") (class "Default")
      (node (ref "Q5") (pin "1") (pinfunction "S1_1") (pintype "passive"))
      (node (ref "Q5") (pin "3") (pinfunction "S2_3") (pintype "passive"))
      (node (ref "U10") (pin "10") (pinfunction "VBUS_C_10") (pintype "passive"))
      (node (ref "USB2") (pin "A4B9") (pinfunction "VBUS_A4B9") (pintype "passive"))
      (node (ref "USB2") (pin "B4A9") (pinfunction "VBUS_B4A9") (pintype "passive"))
    )
    (net (code "75") (name "/cc1") (class "Default")
      (node (ref "R11") (pin "1") (pinfunction "1_1") (pintype "passive"))
      (node (ref "USB1") (pin "A5") (pinfunction "CC1_A5") (pintype "passive"))
    )
    (net (code "76") (name "/cc2") (class "Default")
      (node (ref "R12") (pin "1") (pinfunction "1_1") (pintype "passive"))
      (node (ref "USB1") (pin "B5") (pinfunction "CC2_B5") (pintype "passive"))
    )
    (net (code "77") (name "3V3A") (class "Default")
      (node (ref "C11") (pin "1") (pinfunction "1_1") (pintype "passive"))
      (node (ref "C27") (pin "1") (pinfunction "1_1") (pintype "passive"))
      (node (ref "C28") (pin "2") (pinfunction "2_2") (pintype "passive"))
      (node (ref "C4") (pin "1") (pinfunction "1_1") (pintype "passive"))
      (node (ref "C7") (pin "2") (pinfunction "2_2") (pintype "passive"))
      (node (ref "C9") (pin "2") (pinfunction "2_2") (pintype "passive"))
      (node (ref "CARD1") (pin "4") (pinfunction "VDD_4") (pintype "passive"))
      (node (ref "LED4") (pin "1") (pinfunction "1_1") (pintype "passive"))
      (node (ref "R10") (pin "2") (pinfunction "2_2") (pintype "passive"))
      (node (ref "R13") (pin "1") (pinfunction "1_1") (pintype "passive"))
      (node (ref "R14") (pin "1") (pinfunction "1_1") (pintype "passive"))
      (node (ref "R17") (pin "1") (pinfunction "1_1") (pintype "passive"))
      (node (ref "R20") (pin "1") (pinfunction "1_1") (pintype "passive"))
      (node (ref "R21") (pin "1") (pinfunction "1_1") (pintype "passive"))
      (node (ref "R22") (pin "1") (pinfunction "1_1") (pintype "passive"))
      (node (ref "R8") (pin "2") (pinfunction "2_2") (pintype "passive"))
      (node (ref "U13") (pin "5") (pinfunction "VBAT_5") (pintype "passive"))
      (node (ref "U13") (pin "8") (pinfunction "VDD_8") (pintype "passive"))
      (node (ref "U14") (pin "13") (pinfunction "VDD_13") (pintype "passive"))
      (node (ref "U14") (pin "8") (pinfunction "VLOGIC_8") (pintype "passive"))
      (node (ref "U2") (pin "2") (pinfunction "VOUT_2") (pintype "passive"))
      (node (ref "U2") (pin "4") (pinfunction "TAB_4") (pintype "passive"))
      (node (ref "U4") (pin "1") (pinfunction "VDDA_1") (pintype "passive"))
      (node (ref "U4") (pin "19") (pinfunction "VDD3P3_RTC_19") (pintype "passive"))
      (node (ref "U4") (pin "3") (pinfunction "VDDA3P3_3") (pintype "passive"))
      (node (ref "U4") (pin "37") (pinfunction "VDD3P3_CPU_37") (pintype "passive"))
      (node (ref "U4") (pin "4") (pinfunction "VDDA3P3_4") (pintype "passive"))
      (node (ref "U4") (pin "43") (pinfunction "VDDA_43") (pintype "passive"))
      (node (ref "U4") (pin "46") (pinfunction "VDDA_46") (pintype "passive"))
    )
    (net (code "78") (name "BAT+") (class "Default")
      (node (ref "C5") (pin "1") (pinfunction "1_1") (pintype "passive"))
      (node (ref "C6") (pin "1") (pinfunction "1_1") (pintype "passive"))
      (node (ref "C8") (pin "2") (pinfunction "2_2") (pintype "passive"))
      (node (ref "J2") (pin "2") (pinfunction "2_2") (pintype "passive"))
      (node (ref "R1") (pin "1") (pinfunction "1_1") (pintype "passive"))
      (node (ref "U10") (pin "15") (pinfunction "BAT_15") (pintype "passive"))
    )
    (net (code "79") (name "GND") (class "Default")
      (node (ref "C10") (pin "1") (pinfunction "1_1") (pintype "passive"))
      (node (ref "C11") (pin "2") (pinfunction "2_2") (pintype "passive"))
      (node (ref "C12") (pin "1") (pinfunction "1_1") (pintype "passive"))
      (node (ref "C13") (pin "1") (pinfunction "1_1") (pintype "passive"))
      (node (ref "C14") (pin "1") (pinfunction "1_1") (pintype "passive"))
      (node (ref "C15") (pin "1") (pinfunction "1_1") (pintype "passive"))
      (node (ref "C16") (pin "1") (pinfunction "1_1") (pintype "passive"))
      (node (ref "C17") (pin "1") (pinfunction "1_1") (pintype "passive"))
      (node (ref "C18") (pin "2") (pinfunction "2_2") (pintype "passive"))
      (node (ref "C19") (pin "2") (pinfunction "2_2") (pintype "passive"))
      (node (ref "C21") (pin "1") (pinfunction "1_1") (pintype "passive"))
      (node (ref "C24") (pin "2") (pinfunction "2_2") (pintype "passive"))
      (node (ref "C27") (pin "2") (pinfunction "2_2") (pintype "passive"))
      (node (ref "C28") (pin "1") (pinfunction "1_1") (pintype "passive"))
      (node (ref "C30") (pin "1") (pinfunction "1_1") (pintype "passive"))
      (node (ref "C33") (pin "1") (pinfunction "1_1") (pintype "passive"))
      (node (ref "C4") (pin "2") (pinfunction "2_2") (pintype "passive"))
      (node (ref "C7") (pin "1") (pinfunction "1_1") (pintype "passive"))
      (node (ref "C8") (pin "1") (pinfunction "1_1") (pintype "passive"))
      (node (ref "C9") (pin "1") (pinfunction "1_1") (pintype "passive"))
      (node (ref "CARD1") (pin "11") (pinfunction "G4_11") (pintype "passive"))
      (node (ref "CARD1") (pin "12") (pinfunction "G1_12") (pintype "passive"))
      (node (ref "CARD1") (pin "13") (pinfunction "G2_13") (pintype "passive"))
      (node (ref "CARD1") (pin "6") (pinfunction "VSS_6") (pintype "passive"))
      (node (ref "CARD1") (pin "9") (pinfunction "CD_9") (pintype "passive"))
      (node (ref "J1") (pin "1") (pinfunction "1_1") (pintype "passive"))
      (node (ref "J2") (pin "1") (pinfunction "1_1") (pintype "passive"))
      (node (ref "J5") (pin "2") (pinfunction "2_2") (pintype "passive"))
      (node (ref "LED1") (pin "3") (pinfunction "VSS_3") (pintype "passive"))
      (node (ref "LED2") (pin "3") (pinfunction "VSS_3") (pintype "passive"))
      (node (ref "LED3") (pin "2") (pinfunction "2_2") (pintype "passive"))
      (node (ref "R11") (pin "2") (pinfunction "2_2") (pintype "passive"))
      (node (ref "R12") (pin "2") (pinfunction "2_2") (pintype "passive"))
      (node (ref "R2") (pin "1") (pinfunction "1_1") (pintype "passive"))
      (node (ref "R7") (pin "1") (pinfunction "1_1") (pintype "passive"))
      (node (ref "SW2") (pin "3") (pinfunction "3_3") (pintype "passive"))
      (node (ref "SW2") (pin "4") (pinfunction "4_4") (pintype "passive"))
      (node (ref "U1") (pin "12") (pinfunction "12_12") (pintype "passive"))
      (node (ref "U1") (pin "15") (pinfunction "15_15") (pintype "passive"))
      (node (ref "U1") (pin "18") (pinfunction "18_18") (pintype "passive"))
      (node (ref "U1") (pin "21") (pinfunction "21_21") (pintype "passive"))
      (node (ref "U1") (pin "24") (pinfunction "24_24") (pintype "passive"))
      (node (ref "U1") (pin "3") (pinfunction "3_3") (pintype "passive"))
      (node (ref "U1") (pin "6") (pinfunction "6_6") (pintype "passive"))
      (node (ref "U1") (pin "9") (pinfunction "9_9") (pintype "passive"))
      (node (ref "U10") (pin "13") (pinfunction "AGND_13") (pintype "passive"))
      (node (ref "U10") (pin "24") (pinfunction "LED4/I2C_24") (pintype "passive"))
      (node (ref "U10") (pin "41") (pinfunction "EP_41") (pintype "passive"))
      (node (ref "U11") (pin "4") (pinfunction "GND_4") (pintype "passive"))
      (node (ref "U11") (pin "9") (pinfunction "PAD_9") (pintype "passive"))
      (node (ref "U12") (pin "4") (pinfunction "GND_4") (pintype "passive"))
      (node (ref "U12") (pin "9") (pinfunction "PAD_9") (pintype "passive"))
      (node (ref "U13") (pin "7") (pinfunction "VSS_7") (pintype "passive"))
      (node (ref "U14") (pin "1") (pinfunction "CLKIN_1") (pintype "passive"))
      (node (ref "U14") (pin "11") (pinfunction "FSYNC_11") (pintype "passive"))
      (node (ref "U14") (pin "18") (pinfunction "GND_18") (pintype "passive"))
      (node (ref "U14") (pin "25") (pinfunction "EP_25") (pintype "passive"))
      (node (ref "U14") (pin "9") (pinfunction "AD0_9") (pintype "passive"))
      (node (ref "U2") (pin "1") (pinfunction "GND_1") (pintype "passive"))
      (node (ref "U4") (pin "49") (pinfunction "GND_49") (pintype "passive"))
      (node (ref "U5") (pin "29") (pinfunction "EP_29") (pintype "passive"))
      (node (ref "U5") (pin "3") (pinfunction "GND_3") (pintype "passive"))
      (node (ref "U6") (pin "4") (pinfunction "GND_4") (pintype "passive"))
      (node (ref "U6") (pin "9") (pinfunction "PAD_9") (pintype "passive"))
      (node (ref "U8") (pin "4") (pinfunction "GND_4") (pintype "passive"))
      (node (ref "U8") (pin "9") (pinfunction "PAD_9") (pintype "passive"))
      (node (ref "U9") (pin "1") (pinfunction "A0_1") (pintype "passive"))
      (node (ref "U9") (pin "14") (pinfunction "VSS_14") (pintype "passive"))
      (node (ref "U9") (pin "2") (pinfunction "A1_2") (pintype "passive"))
      (node (ref "U9") (pin "24") (pinfunction "A5_24") (pintype "passive"))
      (node (ref "U9") (pin "25") (pinfunction "EXTCLK_25") (pintype "passive"))
      (node (ref "U9") (pin "3") (pinfunction "A2_3") (pintype "passive"))
      (node (ref "U9") (pin "4") (pinfunction "A3_4") (pintype "passive"))
      (node (ref "U9") (pin "5") (pinfunction "A4_5") (pintype "passive"))
      (node (ref "USB1") (pin "13") (pinfunction "GND_13") (pintype "passive"))
      (node (ref "USB1") (pin "14") (pinfunction "GND_14") (pintype "passive"))
      (node (ref "USB1") (pin "15") (pinfunction "GND_15") (pintype "passive"))
      (node (ref "USB1") (pin "16") (pinfunction "GND_16") (pintype "passive"))
      (node (ref "USB1") (pin "A1B12") (pinfunction "GND_A1B12") (pintype "passive"))
      (node (ref "USB1") (pin "B1A12") (pinfunction "GND_B1A12") (pintype "passive"))
      (node (ref "USB2") (pin "13") (pinfunction "GND_13") (pintype "passive"))
      (node (ref "USB2") (pin "14") (pinfunction "GND_14") (pintype "passive"))
      (node (ref "USB2") (pin "15") (pinfunction "GND_15") (pintype "passive"))
      (node (ref "USB2") (pin "16") (pinfunction "GND_16") (pintype "passive"))
      (node (ref "USB2") (pin "A1B12") (pinfunction "GND_A1B12") (pintype "passive"))
      (node (ref "USB2") (pin "B1A12") (pinfunction "GND_B1A12") (pintype "passive"))
    )
    (net (code "80") (name "Net-(C1-Pad2)") (class "Default")
      (node (ref "C1") (pin "2") (pinfunction "2_2") (pintype "passive"))
      (node (ref "L1") (pin "2") (pinfunction "2_2") (pintype "passive"))
      (node (ref "U10") (pin "2") (pinfunction "SW_2") (pintype "passive"))
      (node (ref "U10") (pin "3") (pinfunction "SW_3") (pintype "passive"))
      (node (ref "U10") (pin "4") (pinfunction "SW_4") (pintype "passive"))
      (node (ref "U10") (pin "5") (pinfunction "SW_5") (pintype "passive"))
      (node (ref "U10") (pin "6") (pinfunction "SW_6") (pintype "passive"))
    )
    (net (code "81") (name "Net-(L3-ANT)") (class "Default")
      (node (ref "L3") (pin "1") (pinfunction "ANT_1") (pintype "passive"))
      (node (ref "U4") (pin "2") (pinfunction "LNA_IN_2") (pintype "passive"))
    )
    (net (code "82") (name "Net-(LED1-DOUT)") (class "Default")
      (node (ref "LED1") (pin "2") (pinfunction "DOUT_2") (pintype "passive"))
      (node (ref "LED2") (pin "4") (pinfunction "DIN_4") (pintype "passive"))
    )
    (net (code "83") (name "Net-(LED2-DOUT)") (class "Default")
      (node (ref "J1") (pin "2") (pinfunction "2_2") (pintype "passive"))
      (node (ref "LED2") (pin "2") (pinfunction "DOUT_2") (pintype "passive"))
    )
    (net (code "84") (name "Net-(LED3-Pad1)") (class "Default")
      (node (ref "LED3") (pin "1") (pinfunction "1_1") (pintype "passive"))
      (node (ref "R3") (pin "1") (pinfunction "1_1") (pintype "passive"))
    )
    (net (code "85") (name "Net-(LED4-Pad2)") (class "Default")
      (node (ref "LED4") (pin "2") (pinfunction "2_2") (pintype "passive"))
      (node (ref "R23") (pin "1") (pinfunction "1_1") (pintype "passive"))
    )
    (net (code "86") (name "Net-(Q3-B)") (class "Default")
      (node (ref "Q3") (pin "1") (pinfunction "B_1") (pintype "passive"))
      (node (ref "R15") (pin "2") (pinfunction "2_2") (pintype "passive"))
    )
    (net (code "87") (name "Net-(Q4-B)") (class "Default")
      (node (ref "Q4") (pin "1") (pinfunction "B_1") (pintype "passive"))
      (node (ref "R16") (pin "2") (pinfunction "2_2") (pintype "passive"))
    )
    (net (code "88") (name "Net-(U5-RST#)") (class "Default")
      (node (ref "R9") (pin "2") (pinfunction "2_2") (pintype "passive"))
      (node (ref "U5") (pin "9") (pinfunction "RST#_9") (pintype "passive"))
    )
    (net (code "89") (name "Net-(U6-OUT1)") (class "Default")
      (node (ref "U6") (pin "2") (pinfunction "OUT1_2") (pintype "passive"))
      (node (ref "U7") (pin "4") (pinfunction "4_4") (pintype "passive"))
    )
    (net (code "90") (name "Net-(U6-OUT2)") (class "Default")
      (node (ref "U6") (pin "3") (pinfunction "OUT2_3") (pintype "passive"))
      (node (ref "U7") (pin "3") (pinfunction "3_3") (pintype "passive"))
    )
    (net (code "91") (name "Net-(U8-OUT1)") (class "Default")
      (node (ref "U7") (pin "2") (pinfunction "2_2") (pintype "passive"))
      (node (ref "U8") (pin "2") (pinfunction "OUT1_2") (pintype "passive"))
    )
    (net (code "92") (name "Net-(U8-OUT2)") (class "Default")
      (node (ref "U7") (pin "1") (pinfunction "1_1") (pintype "passive"))
      (node (ref "U8") (pin "3") (pinfunction "OUT2_3") (pintype "passive"))
    )
    (net (code "93") (name "Net-(U10-BATCSP)") (class "Default")
      (node (ref "C13") (pin "2") (pinfunction "2_2") (pintype "passive"))
      (node (ref "C5") (pin "2") (pinfunction "2_2") (pintype "passive"))
      (node (ref "C6") (pin "2") (pinfunction "2_2") (pintype "passive"))
      (node (ref "L1") (pin "1") (pinfunction "1_1") (pintype "passive"))
      (node (ref "R1") (pin "2") (pinfunction "2_2") (pintype "passive"))
      (node (ref "U10") (pin "14") (pinfunction "BATCSP_14") (pintype "passive"))
    )
    (net (code "94") (name "Net-(U10-BSET{slash}HLED)") (class "Default")
      (node (ref "R3") (pin "2") (pinfunction "2_2") (pintype "passive"))
      (node (ref "U10") (pin "17") (pinfunction "BSET/HLED_17") (pintype "passive"))
    )
    (net (code "95") (name "Net-(U10-BST)") (class "Default")
      (node (ref "C1") (pin "1") (pinfunction "1_1") (pintype "passive"))
      (node (ref "U10") (pin "7") (pinfunction "BST_7") (pintype "passive"))
    )
    (net (code "96") (name "Net-(U10-KEY)") (class "Default")
      (node (ref "SW2") (pin "1") (pinfunction "1_1") (pintype "passive"))
      (node (ref "U10") (pin "19") (pinfunction "KEY_19") (pintype "passive"))
    )
    (net (code "97") (name "Net-(U10-NTC)") (class "Default")
      (node (ref "R2") (pin "2") (pinfunction "2_2") (pintype "passive"))
      (node (ref "U10") (pin "16") (pinfunction "NTC_16") (pintype "passive"))
    )
    (net (code "98") (name "Net-(U10-VCC)") (class "Default")
      (node (ref "C24") (pin "1") (pinfunction "1_1") (pintype "passive"))
      (node (ref "U10") (pin "18") (pinfunction "VCC_18") (pintype "passive"))
    )
    (net (code "99") (name "Net-(U10-VDRV)") (class "Default")
      (node (ref "C18") (pin "1") (pinfunction "1_1") (pintype "passive"))
      (node (ref "U10") (pin "8") (pinfunction "VDRV_8") (pintype "passive"))
    )
    (net (code "100") (name "Net-(U11-OUT1)") (class "Default")
      (node (ref "U11") (pin "2") (pinfunction "OUT1_2") (pintype "passive"))
      (node (ref "U7") (pin "6") (pinfunction "6_6") (pintype "passive"))
    )
    (net (code "101") (name "Net-(U11-OUT2)") (class "Default")
      (node (ref "U11") (pin "3") (pinfunction "OUT2_3") (pintype "passive"))
      (node (ref "U7") (pin "5") (pinfunction "5_5") (pintype "passive"))
    )
    (net (code "102") (name "Net-(U12-OUT1)") (class "Default")
      (node (ref "U12") (pin "2") (pinfunction "OUT1_2") (pintype "passive"))
      (node (ref "U7") (pin "8") (pinfunction "8_8") (pintype "passive"))
    )
    (net (code "103") (name "Net-(U12-OUT2)") (class "Default")
      (node (ref "U12") (pin "3") (pinfunction "OUT2_3") (pintype "passive"))
      (node (ref "U7") (pin "7") (pinfunction "7_7") (pintype "passive"))
    )
    (net (code "104") (name "Net-(U13-C1N)") (class "Default")
      (node (ref "C25") (pin "1") (pinfunction "1_1") (pintype "passive"))
      (node (ref "U13") (pin "4") (pinfunction "C1N_4") (pintype "passive"))
    )
    (net (code "105") (name "Net-(U13-C1P)") (class "Default")
      (node (ref "C25") (pin "2") (pinfunction "2_2") (pintype "passive"))
      (node (ref "U13") (pin "3") (pinfunction "C1P_3") (pintype "passive"))
    )
    (net (code "106") (name "Net-(U13-C2N)") (class "Default")
      (node (ref "C26") (pin "1") (pinfunction "1_1") (pintype "passive"))
      (node (ref "U13") (pin "2") (pinfunction "C2N_2") (pintype "passive"))
    )
    (net (code "107") (name "Net-(U13-C2P)") (class "Default")
      (node (ref "C26") (pin "2") (pinfunction "2_2") (pintype "passive"))
      (node (ref "U13") (pin "1") (pinfunction "C2P_1") (pintype "passive"))
    )
    (net (code "108") (name "Net-(U13-IREF)") (class "Default")
      (node (ref "R7") (pin "2") (pinfunction "2_2") (pintype "passive"))
      (node (ref "U13") (pin "12") (pinfunction "IREF_12") (pintype "passive"))
    )
    (net (code "109") (name "Net-(U13-VCC)") (class "Default")
      (node (ref "C12") (pin "2") (pinfunction "2_2") (pintype "passive"))
      (node (ref "U13") (pin "13") (pinfunction "VCOMH_13") (pintype "passive"))
      (node (ref "U13") (pin "14") (pinfunction "VCC_14") (pintype "passive"))
    )
    (net (code "110") (name "Net-(U14-CPOUT)") (class "Default")
      (node (ref "C33") (pin "2") (pinfunction "2_2") (pintype "passive"))
      (node (ref "U14") (pin "20") (pinfunction "CPOUT_20") (pintype "passive"))
    )
    (net (code "111") (name "Net-(U14-REGOUT)") (class "Default")
      (node (ref "C19") (pin "1") (pinfunction "1_1") (pintype "passive"))
      (node (ref "U14") (pin "10") (pinfunction "REGOUT_10") (pintype "passive"))
    )
    (net (code "112") (name "VBUS_A") (class "Default")
      (node (ref "D1") (pin "2") (pinfunction "A_2") (pintype "passive"))
      (node (ref "J1") (pin "3") (pinfunction "3_3") (pintype "passive"))
      (node (ref "J5") (pin "1") (pinfunction "1_1") (pintype "passive"))
      (node (ref "Q2") (pin "1") (pinfunction "S1_1") (pintype "passive"))
      (node (ref "Q2") (pin "3") (pinfunction "S2_3") (pintype "passive"))
      (node (ref "U1") (pin "11") (pinfunction "11_11") (pintype "passive"))
      (node (ref "U1") (pin "14") (pinfunction "14_14") (pintype "passive"))
      (node (ref "U1") (pin "17") (pinfunction "17_17") (pintype "passive"))
      (node (ref "U1") (pin "2") (pinfunction "2_2") (pintype "passive"))
      (node (ref "U1") (pin "20") (pinfunction "20_20") (pintype "passive"))
      (node (ref "U1") (pin "23") (pinfunction "23_23") (pintype "passive"))
      (node (ref "U1") (pin "5") (pinfunction "5_5") (pintype "passive"))
      (node (ref "U1") (pin "8") (pinfunction "8_8") (pintype "passive"))
      (node (ref "U10") (pin "11") (pinfunction "VBUS_A_11") (pintype "passive"))
      (node (ref "U11") (pin "1") (pinfunction "VM_1") (pintype "passive"))
      (node (ref "U11") (pin "8") (pinfunction "VCC_8") (pintype "passive"))
      (node (ref "U12") (pin "1") (pinfunction "VM_1") (pintype "passive"))
      (node (ref "U12") (pin "8") (pinfunction "VCC_8") (pintype "passive"))
      (node (ref "U6") (pin "1") (pinfunction "VM_1") (pintype "passive"))
      (node (ref "U6") (pin "8") (pinfunction "VCC_8") (pintype "passive"))
      (node (ref "U8") (pin "1") (pinfunction "VM_1") (pintype "passive"))
      (node (ref "U8") (pin "8") (pinfunction "VCC_8") (pintype "passive"))
      (node (ref "U9") (pin "28") (pinfunction "VDD_28") (pintype "passive"))
    )
    (net (code "113") (name "VDD_5V") (class "Default")
      (node (ref "C21") (pin "2") (pinfunction "2_2") (pintype "passive"))
      (node (ref "D1") (pin "1") (pinfunction "C_1") (pintype "passive"))
      (node (ref "LED1") (pin "1") (pinfunction "VDD_1") (pintype "passive"))
      (node (ref "LED2") (pin "1") (pinfunction "VDD_1") (pintype "passive"))
      (node (ref "R9") (pin "1") (pinfunction "1_1") (pintype "passive"))
      (node (ref "U2") (pin "3") (pinfunction "VIN_3") (pintype "passive"))
      (node (ref "U5") (pin "7") (pinfunction "REGIN_7") (pintype "passive"))
      (node (ref "U5") (pin "8") (pinfunction "VBUS_8") (pintype "passive"))
      (node (ref "USB1") (pin "A4B9") (pinfunction "VBUS_A4B9") (pintype "passive"))
      (node (ref "USB1") (pin "B4A9") (pinfunction "VBUS_B4A9") (pintype "passive"))
    )
    (net (code "114") (name "VOUT") (class "Default")
      (node (ref "C14") (pin "2") (pinfunction "2_2") (pintype "passive"))
      (node (ref "C15") (pin "2") (pinfunction "2_2") (pintype "passive"))
      (node (ref "C16") (pin "2") (pinfunction "2_2") (pintype "passive"))
      (node (ref "C17") (pin "2") (pinfunction "2_2") (pintype "passive"))
      (node (ref "Q2") (pin "2") (pinfunction "D_2") (pintype "passive"))
      (node (ref "Q2") (pin "5") (pinfunction "NC_5") (pintype "passive"))
      (node (ref "Q5") (pin "2") (pinfunction "D_2") (pintype "passive"))
      (node (ref "Q5") (pin "5") (pinfunction "NC_5") (pintype "passive"))
      (node (ref "U10") (pin "12") (pinfunction "VOUT_A_12") (pintype "passive"))
      (node (ref "U10") (pin "25") (pinfunction "VOUT_25") (pintype "passive"))
      (node (ref "U10") (pin "26") (pinfunction "VOUT_26") (pintype "passive"))
      (node (ref "U10") (pin "27") (pinfunction "VOUT_27") (pintype "passive"))
      (node (ref "U10") (pin "28") (pinfunction "VOUT_28") (pintype "passive"))
      (node (ref "U10") (pin "29") (pinfunction "VOUT_29") (pintype "passive"))
      (node (ref "U10") (pin "9") (pinfunction "VOUT_C_9") (pintype "passive"))
    )
    (net (code "115") (name "unconnected-(CARD1-DAT1-Pad8)") (class "Default")
      (node (ref "CARD1") (pin "8") (pinfunction "DAT1_8") (pintype "passive+no_connect"))
    )
    (net (code "116") (name "unconnected-(CARD1-DAT2-Pad1)") (class "Default")
      (node (ref "CARD1") (pin "1") (pinfunction "DAT2_1") (pintype "passive+no_connect"))
    )
    (net (code "117") (name "unconnected-(CARD1-G3-Pad10)") (class "Default")
      (node (ref "CARD1") (pin "10") (pinfunction "G3_10") (pintype "passive"))
    )
    (net (code "118") (name "unconnected-(L3-Pad2)") (class "Default")
      (node (ref "L3") (pin "2") (pinfunction "2_2") (pintype "passive"))
    )
    (net (code "119") (name "unconnected-(SW2-Pad2)") (class "Default")
      (node (ref "SW2") (pin "2") (pinfunction "2_2") (pintype "passive"))
    )
    (net (code "120") (name "unconnected-(U4-CAP1_NC-Pad48)") (class "Default")
      (node (ref "U4") (pin "48") (pinfunction "CAP1_NC_48") (pintype "passive+no_connect"))
    )
    (net (code "121") (name "unconnected-(U4-CAP2_NC-Pad47)") (class "Default")
      (node (ref "U4") (pin "47") (pinfunction "CAP2_NC_47") (pintype "passive+no_connect"))
    )
    (net (code "122") (name "unconnected-(U4-VDD_SDIO-Pad26)") (class "Default")
      (node (ref "U4") (pin "26") (pinfunction "VDD_SDIO_26") (pintype "passive+no_connect"))
    )
    (net (code "123") (name "unconnected-(U4-XTAL_N_NC-Pad44)") (class "Default")
      (node (ref "U4") (pin "44") (pinfunction "XTAL_N_NC_44") (pintype "passive+no_connect"))
    )
    (net (code "124") (name "unconnected-(U4-XTAL_P_NC-Pad45)") (class "Default")
      (node (ref "U4") (pin "45") (pinfunction "XTAL_P_NC_45") (pintype "passive+no_connect"))
    )
    (net (code "125") (name "unconnected-(U5-CTS-Pad23)") (class "Default")
      (node (ref "U5") (pin "23") (pinfunction "CTS_23") (pintype "passive+no_connect"))
    )
    (net (code "126") (name "unconnected-(U5-DCD-Pad1)") (class "Default")
      (node (ref "U5") (pin "1") (pinfunction "DCD_1") (pintype "passive+no_connect"))
    )
    (net (code "127") (name "unconnected-(U5-DSR-Pad27)") (class "Default")
      (node (ref "U5") (pin "27") (pinfunction "DSR_27") (pintype "passive+no_connect"))
    )
    (net (code "128") (name "unconnected-(U5-NC-Pad10)") (class "Default")
      (node (ref "U5") (pin "10") (pinfunction "NC_10") (pintype "passive+no_connect"))
    )
    (net (code "129") (name "unconnected-(U5-NC-Pad13)") (class "Default")
      (node (ref "U5") (pin "13") (pinfunction "NC_13") (pintype "passive+no_connect"))
    )
    (net (code "130") (name "unconnected-(U5-NC-Pad14)") (class "Default")
      (node (ref "U5") (pin "14") (pinfunction "NC_14") (pintype "passive+no_connect"))
    )
    (net (code "131") (name "unconnected-(U5-NC-Pad15)") (class "Default")
      (node (ref "U5") (pin "15") (pinfunction "NC_15") (pintype "passive+no_connect"))
    )
    (net (code "132") (name "unconnected-(U5-NC-Pad16)") (class "Default")
      (node (ref "U5") (pin "16") (pinfunction "NC_16") (pintype "passive+no_connect"))
    )
    (net (code "133") (name "unconnected-(U5-NC-Pad17)") (class "Default")
      (node (ref "U5") (pin "17") (pinfunction "NC_17") (pintype "passive+no_connect"))
    )
    (net (code "134") (name "unconnected-(U5-NC-Pad18)") (class "Default")
      (node (ref "U5") (pin "18") (pinfunction "NC_18") (pintype "passive+no_connect"))
    )
    (net (code "135") (name "unconnected-(U5-NC-Pad19)") (class "Default")
      (node (ref "U5") (pin "19") (pinfunction "NC_19") (pintype "passive+no_connect"))
    )
    (net (code "136") (name "unconnected-(U5-NC-Pad20)") (class "Default")
      (node (ref "U5") (pin "20") (pinfunction "NC_20") (pintype "passive+no_connect"))
    )
    (net (code "137") (name "unconnected-(U5-NC-Pad21)") (class "Default")
      (node (ref "U5") (pin "21") (pinfunction "NC_21") (pintype "passive+no_connect"))
    )
    (net (code "138") (name "unconnected-(U5-NC-Pad22)") (class "Default")
      (node (ref "U5") (pin "22") (pinfunction "NC_22") (pintype "passive+no_connect"))
    )
    (net (code "139") (name "unconnected-(U5-RI-Pad2)") (class "Default")
      (node (ref "U5") (pin "2") (pinfunction "RI_2") (pintype "passive+no_connect"))
    )
    (net (code "140") (name "unconnected-(U5-SUSPEND#-Pad11)") (class "Default")
      (node (ref "U5") (pin "11") (pinfunction "SUSPEND#_11") (pintype "passive+no_connect"))
    )
    (net (code "141") (name "unconnected-(U5-SUSPEND-Pad12)") (class "Default")
      (node (ref "U5") (pin "12") (pinfunction "SUSPEND_12") (pintype "passive+no_connect"))
    )
    (net (code "142") (name "unconnected-(U5-VDD-Pad6)") (class "Default")
      (node (ref "U5") (pin "6") (pinfunction "VDD_6") (pintype "passive"))
    )
    (net (code "143") (name "unconnected-(U9-OE#-Pad23)") (class "Default")
      (node (ref "U9") (pin "23") (pinfunction "OE#_23") (pintype "passive"))
    )
    (net (code "144") (name "unconnected-(U10-GATE_B-Pad31)") (class "Default")
      (node (ref "U10") (pin "31") (pinfunction "GATE_B_31") (pintype "passive+no_connect"))
    )
    (net (code "145") (name "unconnected-(U10-IO1-Pad1)") (class "Default")
      (node (ref "U10") (pin "1") (pinfunction "IO1_1") (pintype "passive+no_connect"))
    )
    (net (code "146") (name "unconnected-(U10-IO2-Pad40)") (class "Default")
      (node (ref "U10") (pin "40") (pinfunction "IO2_40") (pintype "passive+no_connect"))
    )
    (net (code "147") (name "unconnected-(U10-LED3{slash}IRQ-Pad23)") (class "Default")
      (node (ref "U10") (pin "23") (pinfunction "LED3/IRQ_23") (pintype "passive+no_connect"))
    )
    (net (code "148") (name "unconnected-(U10-VBUS_B-Pad30)") (class "Default")
      (node (ref "U10") (pin "30") (pinfunction "VBUS_B_30") (pintype "passive+no_connect"))
    )
    (net (code "149") (name "unconnected-(U13-NC-Pad6)") (class "Default")
      (node (ref "U13") (pin "6") (pinfunction "NC_6") (pintype "passive+no_connect"))
    )
    (net (code "150") (name "unconnected-(U14-AUX_CL-Pad7)") (class "Default")
      (node (ref "U14") (pin "7") (pinfunction "AUX_CL_7") (pintype "passive+no_connect"))
    )
    (net (code "151") (name "unconnected-(U14-AUX_DA-Pad6)") (class "Default")
      (node (ref "U14") (pin "6") (pinfunction "AUX_DA_6") (pintype "passive+no_connect"))
    )
    (net (code "152") (name "unconnected-(U14-INT-Pad12)") (class "Default")
      (node (ref "U14") (pin "12") (pinfunction "INT_12") (pintype "passive"))
    )
    (net (code "153") (name "unconnected-(U14-NC-Pad2)") (class "Default")
      (node (ref "U14") (pin "2") (pinfunction "NC_2") (pintype "passive+no_connect"))
    )
    (net (code "154") (name "unconnected-(U14-NC-Pad3)") (class "Default")
      (node (ref "U14") (pin "3") (pinfunction "NC_3") (pintype "passive+no_connect"))
    )
    (net (code "155") (name "unconnected-(U14-NC-Pad4)") (class "Default")
      (node (ref "U14") (pin "4") (pinfunction "NC_4") (pintype "passive+no_connect"))
    )
    (net (code "156") (name "unconnected-(U14-NC-Pad5)") (class "Default")
      (node (ref "U14") (pin "5") (pinfunction "NC_5") (pintype "passive+no_connect"))
    )
    (net (code "157") (name "unconnected-(U14-NC-Pad14)") (class "Default")
      (node (ref "U14") (pin "14") (pinfunction "NC_14") (pintype "passive+no_connect"))
    )
    (net (code "158") (name "unconnected-(U14-NC-Pad15)") (class "Default")
      (node (ref "U14") (pin "15") (pinfunction "NC_15") (pintype "passive+no_connect"))
    )
    (net (code "159") (name "unconnected-(U14-NC-Pad16)") (class "Default")
      (node (ref "U14") (pin "16") (pinfunction "NC_16") (pintype "passive+no_connect"))
    )
    (net (code "160") (name "unconnected-(U14-NC-Pad17)") (class "Default")
      (node (ref "U14") (pin "17") (pinfunction "NC_17") (pintype "passive+no_connect"))
    )
    (net (code "161") (name "unconnected-(U14-RESV-Pad19)") (class "Default")
      (node (ref "U14") (pin "19") (pinfunction "RESV_19") (pintype "passive+no_connect"))
    )
    (net (code "162") (name "unconnected-(U14-RESV-Pad21)") (class "Default")
      (node (ref "U14") (pin "21") (pinfunction "RESV_21") (pintype "passive+no_connect"))
    )
    (net (code "163") (name "unconnected-(U14-RESV-Pad22)") (class "Default")
      (node (ref "U14") (pin "22") (pinfunction "RESV_22") (pintype "passive+no_connect"))
    )
    (net (code "164") (name "unconnected-(USB1-SBU1-PadA8)") (class "Default")
      (node (ref "USB1") (pin "A8") (pinfunction "SBU1_A8") (pintype "passive+no_connect"))
    )
    (net (code "165") (name "unconnected-(USB1-SBU2-PadB8)") (class "Default")
      (node (ref "USB1") (pin "B8") (pinfunction "SBU2_B8") (pintype "passive+no_connect"))
    )
    (net (code "166") (name "unconnected-(USB2-SBU1-PadA8)") (class "Default")
      (node (ref "USB2") (pin "A8") (pinfunction "SBU1_A8") (pintype "passive+no_connect"))
    )
    (net (code "167") (name "unconnected-(USB2-SBU2-PadB8)") (class "Default")
      (node (ref "USB2") (pin "B8") (pinfunction "SBU2_B8") (pintype "passive+no_connect"))
    )
  )
)
